# driver.net
KiCad netlist of a schematic drawn in EAGLE
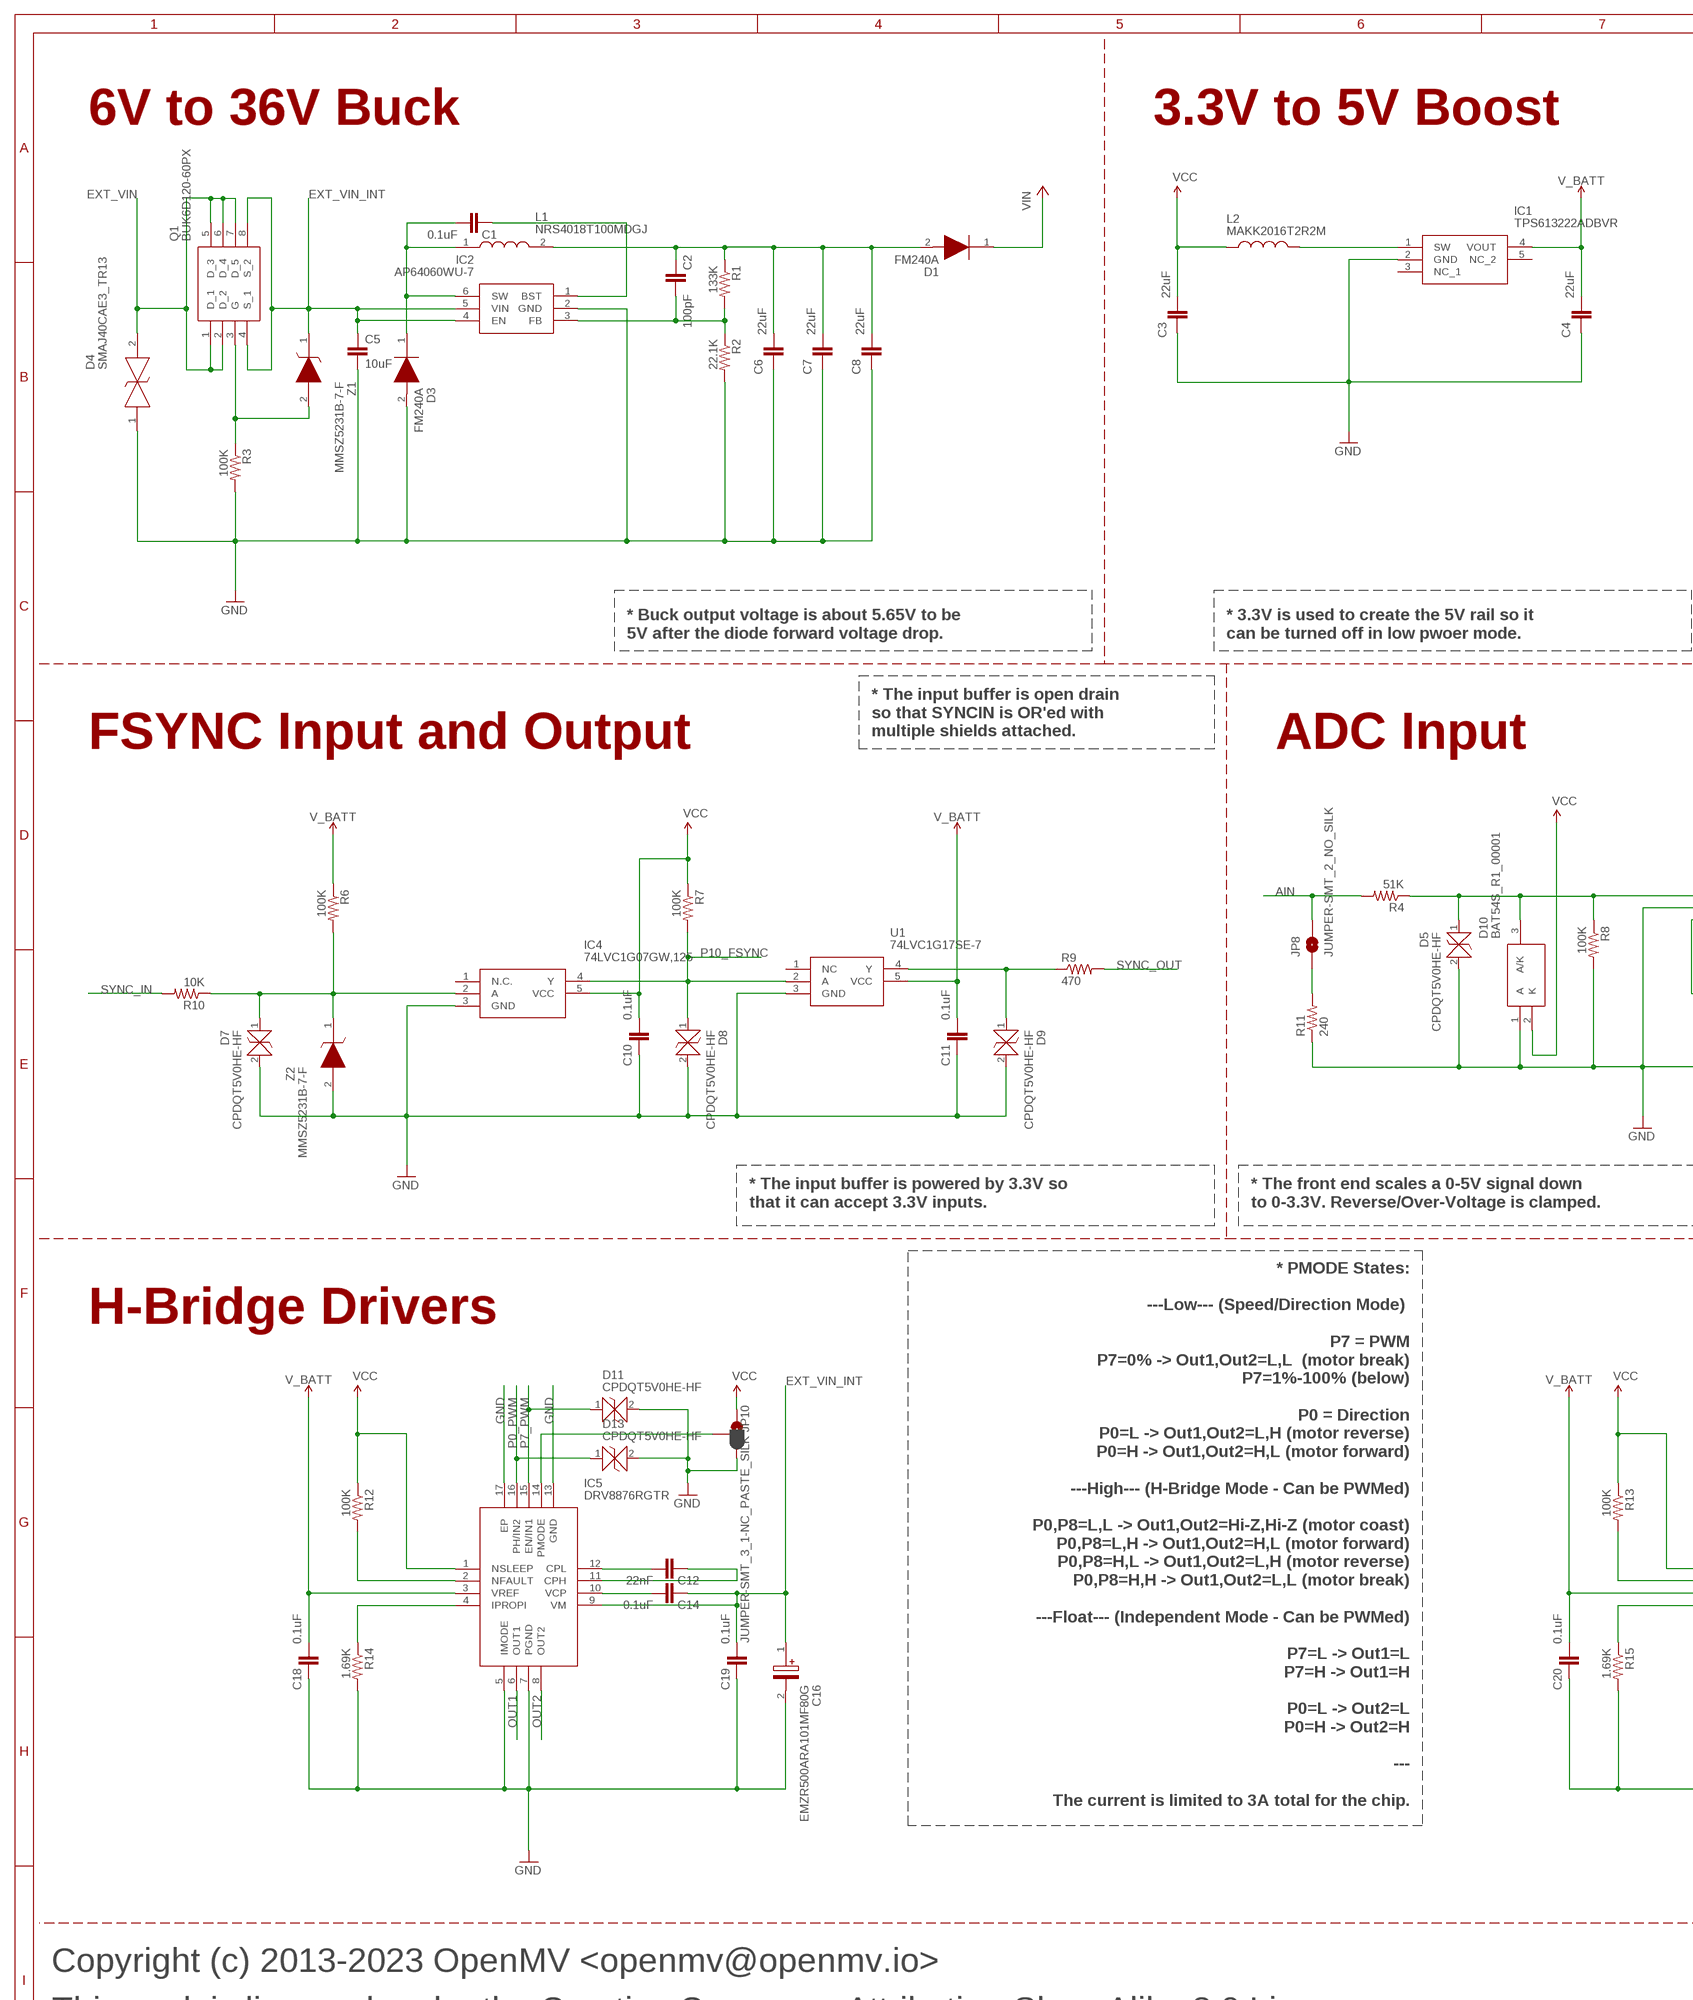
[diagram p0: schematic, sheet 1, part 1 of 2]
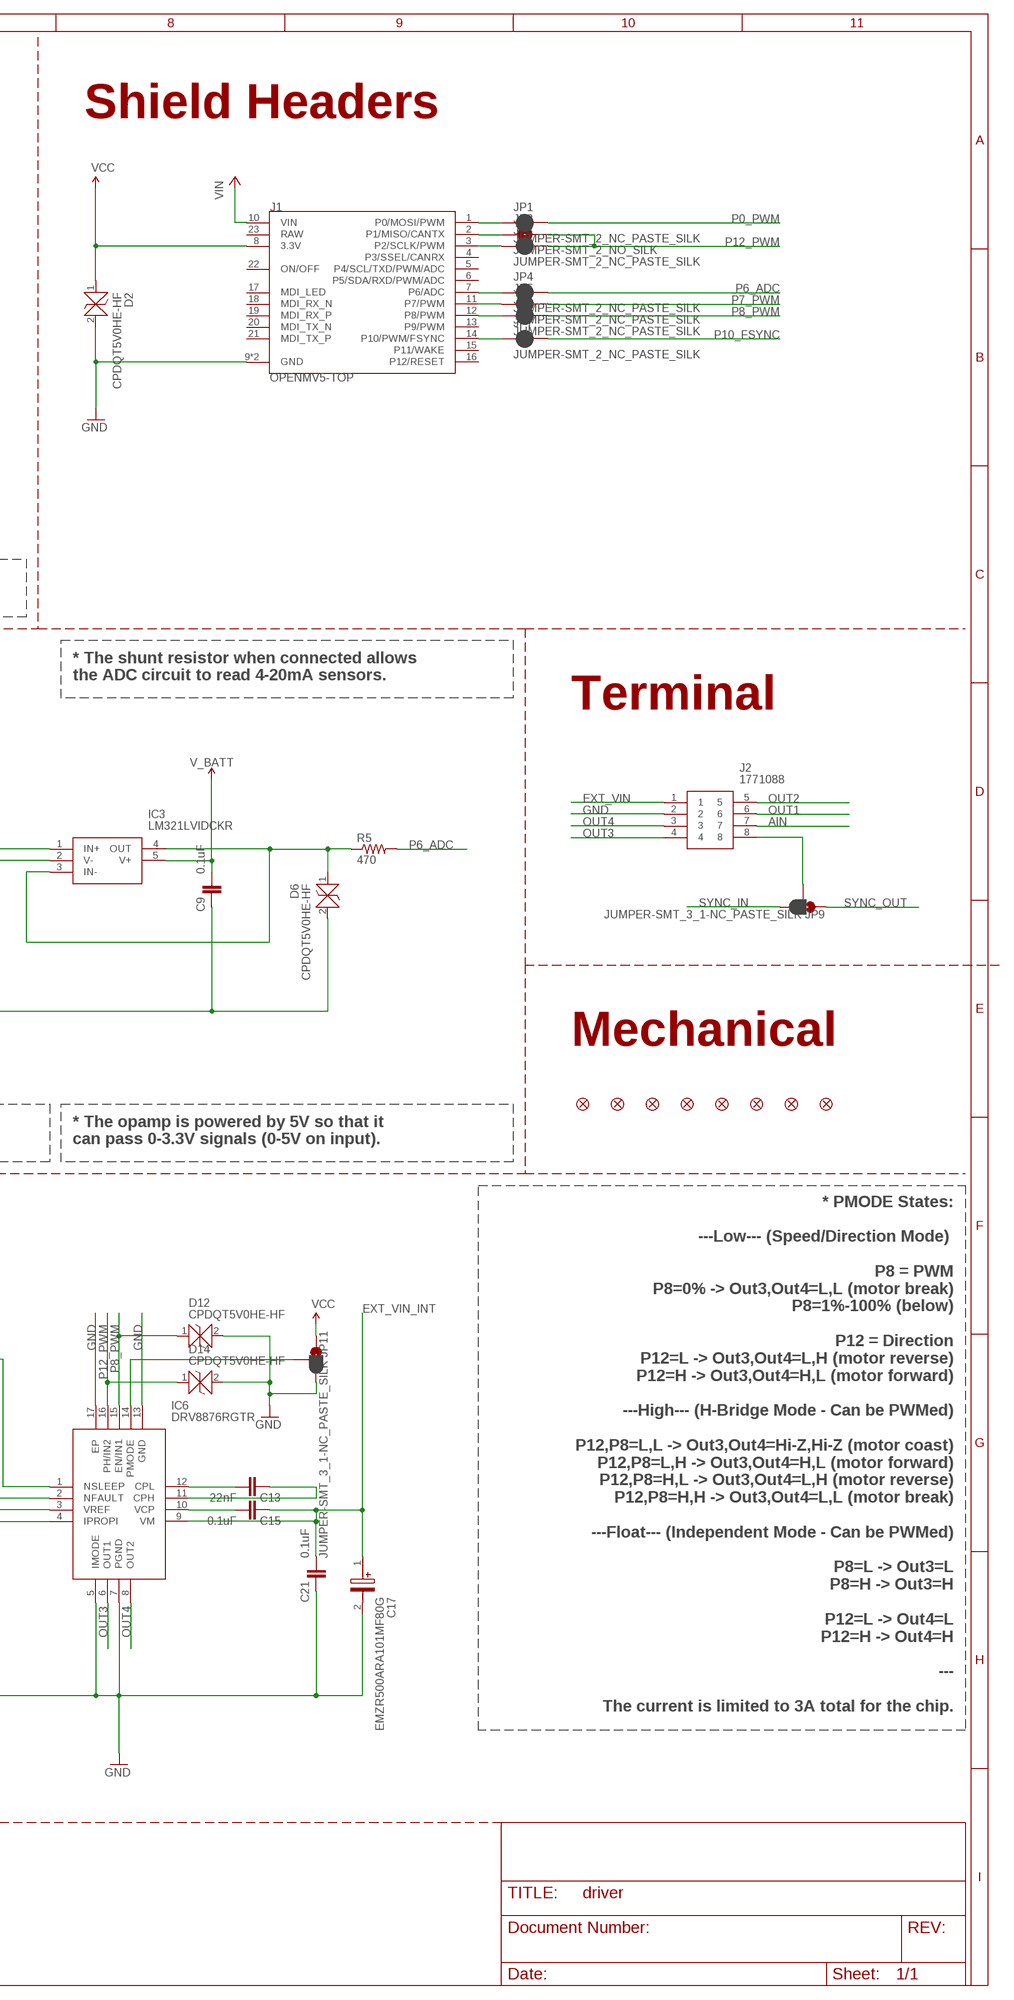
[diagram p1: schematic, sheet 1, part 2 of 2]

(export (version "E")
  (design (tool "Eeschema 10.0.6"))
  (components
    (comp (ref "C1")
      (value "0.1uF")
      (footprint "eagle-import:0402-CAP")
      (fields (field (name "MPN") "GRM155R71H104KE14D"))
      (libsource (lib "eagle-import") (part "CAP0402-CAP"))
    )
    (comp (ref "C2")
      (value "100pF")
      (footprint "eagle-import:0402-CAP")
      (fields (field (name "MPN") "CC0402JRNPO9BN101"))
      (libsource (lib "eagle-import") (part "CAP0402-CAP"))
    )
    (comp (ref "C3")
      (value "22uF")
      (footprint "eagle-import:0805")
      (fields (field (name "MPN") "CL21A226MQQNNNE"))
      (libsource (lib "eagle-import") (part "22UF-0805-6.3V-20%"))
    )
    (comp (ref "C4")
      (value "22uF")
      (footprint "eagle-import:0805")
      (fields (field (name "MPN") "CL21A226MQQNNNE"))
      (libsource (lib "eagle-import") (part "22UF-0805-6.3V-20%"))
    )
    (comp (ref "C5")
      (value "10uF")
      (footprint "eagle-import:C0805")
      (fields (field (name "MPN") "GRM21BR61H106KE43K"))
      (libsource (lib "eagle-import") (part "C-EUC0805"))
    )
    (comp (ref "C6")
      (value "22uF")
      (footprint "eagle-import:0805")
      (fields (field (name "MPN") "CL21A226MQQNNNE"))
      (libsource (lib "eagle-import") (part "22UF-0805-6.3V-20%"))
    )
    (comp (ref "C7")
      (value "22uF")
      (footprint "eagle-import:0805")
      (fields (field (name "MPN") "CL21A226MQQNNNE"))
      (libsource (lib "eagle-import") (part "22UF-0805-6.3V-20%"))
    )
    (comp (ref "C8")
      (value "22uF")
      (footprint "eagle-import:0805")
      (fields (field (name "MPN") "CL21A226MQQNNNE"))
      (libsource (lib "eagle-import") (part "22UF-0805-6.3V-20%"))
    )
    (comp (ref "C9")
      (value "0.1uF")
      (footprint "eagle-import:0402-CAP")
      (fields (field (name "MPN") "GRM155R71H104KE14D"))
      (libsource (lib "eagle-import") (part "CAP0402-CAP"))
    )
    (comp (ref "C10")
      (value "0.1uF")
      (footprint "eagle-import:0402-CAP")
      (fields (field (name "MPN") "GRM155R71H104KE14D"))
      (libsource (lib "eagle-import") (part "CAP0402-CAP"))
    )
    (comp (ref "C11")
      (value "0.1uF")
      (footprint "eagle-import:0402-CAP")
      (fields (field (name "MPN") "GRM155R71H104KE14D"))
      (libsource (lib "eagle-import") (part "CAP0402-CAP"))
    )
    (comp (ref "C12")
      (value "22nF")
      (footprint "eagle-import:0402-CAP")
      (fields (field (name "MPN") "GRM155R71H223KA12D"))
      (libsource (lib "eagle-import") (part "CAP0402-CAP"))
    )
    (comp (ref "C13")
      (value "22nF")
      (footprint "eagle-import:0402-CAP")
      (fields (field (name "MPN") "GRM155R71H223KA12D"))
      (libsource (lib "eagle-import") (part "CAP0402-CAP"))
    )
    (comp (ref "C14")
      (value "0.1uF")
      (footprint "eagle-import:0402-CAP")
      (fields (field (name "MPN") "GRM155R71H104KE14D"))
      (libsource (lib "eagle-import") (part "CAP0402-CAP"))
    )
    (comp (ref "C15")
      (value "0.1uF")
      (footprint "eagle-import:0402-CAP")
      (fields (field (name "MPN") "GRM155R71H104KE14D"))
      (libsource (lib "eagle-import") (part "CAP0402-CAP"))
    )
    (comp (ref "C16")
      (value "EMZR500ARA101MF80G")
      (footprint "eagle-import:CAPAE660X820N")
      (fields (field (name "MOUSER_PART_NUMBER") "661-EMZR500ARA101MF8"))
      (libsource (lib "eagle-import") (part "EMZR500ARA101MF80G"))
    )
    (comp (ref "C17")
      (value "EMZR500ARA101MF80G")
      (footprint "eagle-import:CAPAE660X820N")
      (fields (field (name "MOUSER_PART_NUMBER") "661-EMZR500ARA101MF8"))
      (libsource (lib "eagle-import") (part "EMZR500ARA101MF80G"))
    )
    (comp (ref "C18")
      (value "0.1uF")
      (footprint "eagle-import:0402-CAP")
      (fields (field (name "MPN") "GRM155R71H104KE14D"))
      (libsource (lib "eagle-import") (part "CAP0402-CAP"))
    )
    (comp (ref "C19")
      (value "0.1uF")
      (footprint "eagle-import:0402-CAP")
      (fields (field (name "MPN") "GRM155R71H104KE14D"))
      (libsource (lib "eagle-import") (part "CAP0402-CAP"))
    )
    (comp (ref "C20")
      (value "0.1uF")
      (footprint "eagle-import:0402-CAP")
      (fields (field (name "MPN") "GRM155R71H104KE14D"))
      (libsource (lib "eagle-import") (part "CAP0402-CAP"))
    )
    (comp (ref "C21")
      (value "0.1uF")
      (footprint "eagle-import:0402-CAP")
      (fields (field (name "MPN") "GRM155R71H104KE14D"))
      (libsource (lib "eagle-import") (part "CAP0402-CAP"))
    )
    (comp (ref "D1")
      (value "FM240A")
      (footprint "eagle-import:DIOM5025X231N")
      (fields (field (name "MOUSER_PART_NUMBER") "583-FM240A"))
      (libsource (lib "eagle-import") (part "FM240A"))
    )
    (comp (ref "D2")
      (value "CPDQT5V0HE-HF")
      (footprint "eagle-import:CPDQT5V0HEHF")
      (libsource (lib "eagle-import") (part "CPDQT5V0HE-HF"))
    )
    (comp (ref "D3")
      (value "FM240A")
      (footprint "eagle-import:DIOM5025X231N")
      (fields (field (name "MOUSER_PART_NUMBER") "583-FM240A"))
      (libsource (lib "eagle-import") (part "FM240A"))
    )
    (comp (ref "D4")
      (value "SMAJ40CAE3_TR13")
      (footprint "eagle-import:SMAJ40CAE3TR13")
      (fields
        (field (name "MANUFACTURER_PART_NUMBER") "SMAJ40CAe3/TR13")
        (field (name "MOUSER_PART_NUMBER") "494-SMAJ40CAE3/TR13")
      )
      (libsource (lib "eagle-import") (part "SMAJ40CAE3_TR13"))
    )
    (comp (ref "D5")
      (value "CPDQT5V0HE-HF")
      (footprint "eagle-import:CPDQT5V0HEHF")
      (libsource (lib "eagle-import") (part "CPDQT5V0HE-HF"))
    )
    (comp (ref "D6")
      (value "CPDQT5V0HE-HF")
      (footprint "eagle-import:CPDQT5V0HEHF")
      (libsource (lib "eagle-import") (part "CPDQT5V0HE-HF"))
    )
    (comp (ref "D7")
      (value "CPDQT5V0HE-HF")
      (footprint "eagle-import:CPDQT5V0HEHF")
      (libsource (lib "eagle-import") (part "CPDQT5V0HE-HF"))
    )
    (comp (ref "D8")
      (value "CPDQT5V0HE-HF")
      (footprint "eagle-import:CPDQT5V0HEHF")
      (libsource (lib "eagle-import") (part "CPDQT5V0HE-HF"))
    )
    (comp (ref "D9")
      (value "CPDQT5V0HE-HF")
      (footprint "eagle-import:CPDQT5V0HEHF")
      (libsource (lib "eagle-import") (part "CPDQT5V0HE-HF"))
    )
    (comp (ref "D10")
      (value "BAT54S_R1_00001")
      (footprint "eagle-import:SOT95P240X110-3N")
      (fields (field (name "MOUSER_PART_NUMBER") "241-BAT54S_R1_00001"))
      (libsource (lib "eagle-import") (part "BAT54S_R1_00001"))
    )
    (comp (ref "D11")
      (value "CPDQT5V0HE-HF")
      (footprint "eagle-import:CPDQT5V0HEHF")
      (libsource (lib "eagle-import") (part "CPDQT5V0HE-HF"))
    )
    (comp (ref "D12")
      (value "CPDQT5V0HE-HF")
      (footprint "eagle-import:CPDQT5V0HEHF")
      (libsource (lib "eagle-import") (part "CPDQT5V0HE-HF"))
    )
    (comp (ref "D13")
      (value "CPDQT5V0HE-HF")
      (footprint "eagle-import:CPDQT5V0HEHF")
      (libsource (lib "eagle-import") (part "CPDQT5V0HE-HF"))
    )
    (comp (ref "D14")
      (value "CPDQT5V0HE-HF")
      (footprint "eagle-import:CPDQT5V0HEHF")
      (libsource (lib "eagle-import") (part "CPDQT5V0HE-HF"))
    )
    (comp (ref "FD1")
      (value "FIDUCIAL1X2")
      (footprint "eagle-import:FIDUCIAL-1X2")
      (libsource (lib "eagle-import") (part "FIDUCIAL1X2"))
    )
    (comp (ref "FD2")
      (value "FIDUCIAL1X2")
      (footprint "eagle-import:FIDUCIAL-1X2")
      (libsource (lib "eagle-import") (part "FIDUCIAL1X2"))
    )
    (comp (ref "FD3")
      (value "FIDUCIAL1X2")
      (footprint "eagle-import:FIDUCIAL-1X2")
      (libsource (lib "eagle-import") (part "FIDUCIAL1X2"))
    )
    (comp (ref "FD4")
      (value "FIDUCIAL1X2")
      (footprint "eagle-import:FIDUCIAL-1X2")
      (libsource (lib "eagle-import") (part "FIDUCIAL1X2"))
    )
    (comp (ref "FD5")
      (value "FIDUCIAL1X2")
      (footprint "eagle-import:FIDUCIAL-1X2")
      (libsource (lib "eagle-import") (part "FIDUCIAL1X2"))
    )
    (comp (ref "FD6")
      (value "FIDUCIAL1X2")
      (footprint "eagle-import:FIDUCIAL-1X2")
      (libsource (lib "eagle-import") (part "FIDUCIAL1X2"))
    )
    (comp (ref "FD7")
      (value "FIDUCIAL1X2")
      (footprint "eagle-import:FIDUCIAL-1X2")
      (libsource (lib "eagle-import") (part "FIDUCIAL1X2"))
    )
    (comp (ref "FD8")
      (value "FIDUCIAL1X2")
      (footprint "eagle-import:FIDUCIAL-1X2")
      (libsource (lib "eagle-import") (part "FIDUCIAL1X2"))
    )
    (comp (ref "IC1")
      (value "TPS613222ADBVR")
      (footprint "eagle-import:SOT95P280X145-5N")
      (fields (field (name "MOUSER_PART_NUMBER") "595-TPS613222ADBVR"))
      (libsource (lib "eagle-import") (part "TPS613222ADBVR"))
    )
    (comp (ref "IC2")
      (value "AP64060WU-7")
      (footprint "eagle-import:SOT95P280X100-6N")
      (fields (field (name "MOUSER_PART_NUMBER") "621-AP64060WU-7"))
      (libsource (lib "eagle-import") (part "AP64060WU-7"))
    )
    (comp (ref "IC3")
      (value "LM321LVIDCKR")
      (footprint "eagle-import:SOT65P210X110-5N")
      (fields (field (name "MOUSER_PART_NUMBER") "595-LM321LVIDCKR"))
      (libsource (lib "eagle-import") (part "LM321LVIDCKR"))
    )
    (comp (ref "IC4")
      (value "74LVC1G07GW,125")
      (footprint "eagle-import:SOT65P212X110-5N")
      (fields (field (name "MOUSER_PART_NUMBER") "771-74LVC1G07GW-G"))
      (libsource (lib "eagle-import") (part "74LVC1G07GW,125"))
    )
    (comp (ref "IC5")
      (value "DRV8876RGTR")
      (footprint "eagle-import:QFN50P300X300X100-17N")
      (fields (field (name "MOUSER_PART_NUMBER") "595-DRV8876RGTR"))
      (libsource (lib "eagle-import") (part "DRV8876RGTR"))
    )
    (comp (ref "IC6")
      (value "DRV8876RGTR")
      (footprint "eagle-import:QFN50P300X300X100-17N")
      (fields (field (name "MOUSER_PART_NUMBER") "595-DRV8876RGTR"))
      (libsource (lib "eagle-import") (part "DRV8876RGTR"))
    )
    (comp (ref "J1")
      (value "OPENMV5-TOP")
      (footprint "eagle-import:OPENMV5-TOP")
      (libsource (lib "eagle-import") (part "OPENMV5-TOP"))
    )
    (comp (ref "J2")
      (value "1771088")
      (footprint "eagle-import:1771088")
      (fields (field (name "MOUSER_PART_NUMBER") "651-1771088"))
      (libsource (lib "eagle-import") (part "1771088"))
    )
    (comp (ref "JP1")
      (value "JUMPER-SMT_2_NC_PASTE_SILK")
      (footprint "eagle-import:SMT-JUMPER_2_NC_PASTE_SILK")
      (libsource (lib "eagle-import") (part "JUMPER-SMT_2_NC_PASTE_SILK"))
    )
    (comp (ref "JP2")
      (value "JUMPER-SMT_2_NO_SILK")
      (footprint "eagle-import:SMT-JUMPER_2_NO_SILK")
      (libsource (lib "eagle-import") (part "JUMPER-SMT_2_NO_SILK"))
    )
    (comp (ref "JP3")
      (value "JUMPER-SMT_2_NC_PASTE_SILK")
      (footprint "eagle-import:SMT-JUMPER_2_NC_PASTE_SILK")
      (libsource (lib "eagle-import") (part "JUMPER-SMT_2_NC_PASTE_SILK"))
    )
    (comp (ref "JP4")
      (value "JUMPER-SMT_2_NC_PASTE_SILK")
      (footprint "eagle-import:SMT-JUMPER_2_NC_PASTE_SILK")
      (libsource (lib "eagle-import") (part "JUMPER-SMT_2_NC_PASTE_SILK"))
    )
    (comp (ref "JP5")
      (value "JUMPER-SMT_2_NC_PASTE_SILK")
      (footprint "eagle-import:SMT-JUMPER_2_NC_PASTE_SILK")
      (libsource (lib "eagle-import") (part "JUMPER-SMT_2_NC_PASTE_SILK"))
    )
    (comp (ref "JP6")
      (value "JUMPER-SMT_2_NC_PASTE_SILK")
      (footprint "eagle-import:SMT-JUMPER_2_NC_PASTE_SILK")
      (libsource (lib "eagle-import") (part "JUMPER-SMT_2_NC_PASTE_SILK"))
    )
    (comp (ref "JP7")
      (value "JUMPER-SMT_2_NC_PASTE_SILK")
      (footprint "eagle-import:SMT-JUMPER_2_NC_PASTE_SILK")
      (libsource (lib "eagle-import") (part "JUMPER-SMT_2_NC_PASTE_SILK"))
    )
    (comp (ref "JP8")
      (value "JUMPER-SMT_2_NO_SILK")
      (footprint "eagle-import:SMT-JUMPER_2_NO_SILK")
      (libsource (lib "eagle-import") (part "JUMPER-SMT_2_NO_SILK"))
    )
    (comp (ref "JP9")
      (value "JUMPER-SMT_3_1-NC_PASTE_SILK")
      (footprint "eagle-import:SMT-JUMPER_3_1-NC_PASTE_SILK")
      (libsource (lib "eagle-import") (part "JUMPER-SMT_3_1-NC_PASTE_SILK"))
    )
    (comp (ref "JP10")
      (value "JUMPER-SMT_3_1-NC_PASTE_SILK")
      (footprint "eagle-import:SMT-JUMPER_3_1-NC_PASTE_SILK")
      (libsource (lib "eagle-import") (part "JUMPER-SMT_3_1-NC_PASTE_SILK"))
    )
    (comp (ref "JP11")
      (value "JUMPER-SMT_3_1-NC_PASTE_SILK")
      (footprint "eagle-import:SMT-JUMPER_3_1-NC_PASTE_SILK")
      (libsource (lib "eagle-import") (part "JUMPER-SMT_3_1-NC_PASTE_SILK"))
    )
    (comp (ref "L1")
      (value "NRS4018T100MDGJ")
      (footprint "eagle-import:NRS4018T100MDGJ")
      (fields (field (name "MOUSER_PART_NUMBER") "963-NRS4018T100MDGJ"))
      (libsource (lib "eagle-import") (part "NRS4018T100MDGJ"))
    )
    (comp (ref "L2")
      (value "MAKK2016T2R2M")
      (footprint "eagle-import:INDC2016X100N")
      (fields (field (name "MF") "Taiyo Yuden"))
      (libsource (lib "eagle-import") (part "MAKK2016T2R2M"))
    )
    (comp (ref "Q1")
      (value "BUK6D120-60PX")
      (footprint "eagle-import:BUK6D12060PX")
      (fields (field (name "MOUSER_PART_NUMBER") "771-BUK6D120-60PX"))
      (libsource (lib "eagle-import") (part "BUK6D120-60PX"))
    )
    (comp (ref "R1")
      (value "133K")
      (footprint "eagle-import:0402-RES")
      (fields (field (name "MPN") "RC0402FR-07133KL"))
      (libsource (lib "eagle-import") (part "RESISTOR0402-RES"))
    )
    (comp (ref "R2")
      (value "22.1K")
      (footprint "eagle-import:0402-RES")
      (fields (field (name "MPN") "CR0402-FX-2212GLF"))
      (libsource (lib "eagle-import") (part "RESISTOR0402-RES"))
    )
    (comp (ref "R3")
      (value "100K")
      (footprint "eagle-import:0402-RES")
      (fields (field (name "MPN") "AC0402FR-07100KL"))
      (libsource (lib "eagle-import") (part "RESISTOR0402-RES"))
    )
    (comp (ref "R4")
      (value "51K")
      (footprint "eagle-import:0402-RES")
      (fields (field (name "MPN") "RC0402JR-0751KL"))
      (libsource (lib "eagle-import") (part "RESISTOR0402-RES"))
    )
    (comp (ref "R5")
      (value "470")
      (footprint "eagle-import:R0603")
      (fields (field (name "MPN") "CR0603-FX-4700ELF"))
      (libsource (lib "eagle-import") (part "R-US_R0603"))
    )
    (comp (ref "R6")
      (value "100K")
      (footprint "eagle-import:0402-RES")
      (fields (field (name "MPN") "AC0402FR-07100KL"))
      (libsource (lib "eagle-import") (part "RESISTOR0402-RES"))
    )
    (comp (ref "R7")
      (value "100K")
      (footprint "eagle-import:0402-RES")
      (fields (field (name "MPN") "AC0402FR-07100KL"))
      (libsource (lib "eagle-import") (part "RESISTOR0402-RES"))
    )
    (comp (ref "R8")
      (value "100K")
      (footprint "eagle-import:0402-RES")
      (fields (field (name "MPN") "AC0402FR-07100KL"))
      (libsource (lib "eagle-import") (part "RESISTOR0402-RES"))
    )
    (comp (ref "R9")
      (value "470")
      (footprint "eagle-import:R0603")
      (fields (field (name "MPN") "CR0603-FX-4700ELF"))
      (libsource (lib "eagle-import") (part "R-US_R0603"))
    )
    (comp (ref "R10")
      (value "10K")
      (footprint "eagle-import:0402-RES")
      (fields (field (name "MPN") "AC0402FR-1310KL"))
      (libsource (lib "eagle-import") (part "RESISTOR0402-RES"))
    )
    (comp (ref "R11")
      (value "240")
      (footprint "eagle-import:R0603")
      (fields (field (name "MPN") "RK73B1JTTD241J"))
      (libsource (lib "eagle-import") (part "R-US_R0603"))
    )
    (comp (ref "R12")
      (value "100K")
      (footprint "eagle-import:0402-RES")
      (fields (field (name "MPN") "AC0402FR-07100KL"))
      (libsource (lib "eagle-import") (part "RESISTOR0402-RES"))
    )
    (comp (ref "R13")
      (value "100K")
      (footprint "eagle-import:0402-RES")
      (fields (field (name "MPN") "AC0402FR-07100KL"))
      (libsource (lib "eagle-import") (part "RESISTOR0402-RES"))
    )
    (comp (ref "R14")
      (value "1.69K")
      (footprint "eagle-import:0402-RES")
      (fields (field (name "MPN") "RC0402FR-07169RL"))
      (libsource (lib "eagle-import") (part "RESISTOR0402-RES"))
    )
    (comp (ref "R15")
      (value "1.69K")
      (footprint "eagle-import:0402-RES")
      (fields (field (name "MPN") "RC0402FR-07169RL"))
      (libsource (lib "eagle-import") (part "RESISTOR0402-RES"))
    )
    (comp (ref "U1")
      (value "74LVC1G17SE-7")
      (footprint "eagle-import:SOT65P210X110-5N")
      (fields (field (name "MOUSER_PART_NUMBER") "621-74LVC1G17SE-7"))
      (libsource (lib "eagle-import") (part "74LVC1G17SE-7"))
    )
    (comp (ref "Z1")
      (value "MMSZ5231B-7-F")
      (footprint "eagle-import:SOD3716X145N")
      (fields (field (name "MOUSER_PART_NUMBER") "621-MMSZ5231B-F"))
      (libsource (lib "eagle-import") (part "MMSZ5231B-7-F"))
    )
    (comp (ref "Z2")
      (value "MMSZ5231B-7-F")
      (footprint "eagle-import:SOD3716X145N")
      (fields (field (name "MOUSER_PART_NUMBER") "621-MMSZ5231B-F"))
      (libsource (lib "eagle-import") (part "MMSZ5231B-7-F"))
    )
  )
  (nets
    (net (code "1") (name "/AIN") (class "Default")
      (node (ref "J2") (pin "7") (pinfunction "7_7") (pintype "bidirectional"))
      (node (ref "JP8") (pin "2") (pinfunction "2_2") (pintype "passive"))
      (node (ref "R4") (pin "2") (pinfunction "2_2") (pintype "passive"))
    )
    (net (code "2") (name "/EXT_VIN") (class "Default")
      (node (ref "D4") (pin "2") (pinfunction "2_2") (pintype "bidirectional"))
      (node (ref "J2") (pin "1") (pinfunction "1_1") (pintype "bidirectional"))
      (node (ref "Q1") (pin "1") (pinfunction "D_1_1") (pintype "bidirectional"))
      (node (ref "Q1") (pin "2") (pinfunction "D_2_2") (pintype "bidirectional"))
      (node (ref "Q1") (pin "5") (pinfunction "D_3_5") (pintype "bidirectional"))
      (node (ref "Q1") (pin "6") (pinfunction "D_4_6") (pintype "bidirectional"))
      (node (ref "Q1") (pin "7") (pinfunction "D_5_7") (pintype "bidirectional"))
    )
    (net (code "3") (name "/EXT_VIN_INT") (class "Default")
      (node (ref "C14") (pin "1") (pinfunction "1_1") (pintype "passive"))
      (node (ref "C15") (pin "1") (pinfunction "1_1") (pintype "passive"))
      (node (ref "C16") (pin "1") (pinfunction "+_1") (pintype "bidirectional"))
      (node (ref "C17") (pin "1") (pinfunction "+_1") (pintype "bidirectional"))
      (node (ref "C19") (pin "2") (pinfunction "2_2") (pintype "passive"))
      (node (ref "C21") (pin "2") (pinfunction "2_2") (pintype "passive"))
      (node (ref "C5") (pin "1") (pinfunction "1_1") (pintype "passive"))
      (node (ref "IC2") (pin "4") (pinfunction "EN_4") (pintype "bidirectional"))
      (node (ref "IC2") (pin "5") (pinfunction "VIN_5") (pintype "bidirectional"))
      (node (ref "IC5") (pin "9") (pinfunction "VM_9") (pintype "bidirectional"))
      (node (ref "IC6") (pin "9") (pinfunction "VM_9") (pintype "bidirectional"))
      (node (ref "Q1") (pin "4") (pinfunction "S_1_4") (pintype "bidirectional"))
      (node (ref "Q1") (pin "8") (pinfunction "S_2_8") (pintype "bidirectional"))
      (node (ref "Z1") (pin "1") (pinfunction "K_1") (pintype "bidirectional"))
    )
    (net (code "4") (name "/OUT1") (class "Default")
      (node (ref "IC5") (pin "6") (pinfunction "OUT1_6") (pintype "bidirectional"))
      (node (ref "J2") (pin "6") (pinfunction "6_6") (pintype "bidirectional"))
    )
    (net (code "5") (name "/OUT2") (class "Default")
      (node (ref "IC5") (pin "8") (pinfunction "OUT2_8") (pintype "bidirectional"))
      (node (ref "J2") (pin "5") (pinfunction "5_5") (pintype "bidirectional"))
    )
    (net (code "6") (name "/OUT3") (class "Default")
      (node (ref "IC6") (pin "6") (pinfunction "OUT1_6") (pintype "bidirectional"))
      (node (ref "J2") (pin "4") (pinfunction "4_4") (pintype "bidirectional"))
    )
    (net (code "7") (name "/OUT4") (class "Default")
      (node (ref "IC6") (pin "8") (pinfunction "OUT2_8") (pintype "bidirectional"))
      (node (ref "J2") (pin "3") (pinfunction "3_3") (pintype "bidirectional"))
    )
    (net (code "8") (name "/P0_PWM") (class "Default")
      (node (ref "D13") (pin "1") (pinfunction "1_1") (pintype "bidirectional"))
      (node (ref "IC5") (pin "16") (pinfunction "PH/IN2_16") (pintype "bidirectional"))
      (node (ref "JP1") (pin "2") (pinfunction "2_2") (pintype "passive"))
    )
    (net (code "9") (name "/P6_ADC") (class "Default")
      (node (ref "JP4") (pin "2") (pinfunction "2_2") (pintype "passive"))
      (node (ref "R5") (pin "2") (pinfunction "2_2") (pintype "passive"))
    )
    (net (code "10") (name "/P7_PWM") (class "Default")
      (node (ref "D11") (pin "1") (pinfunction "1_1") (pintype "bidirectional"))
      (node (ref "IC5") (pin "15") (pinfunction "EN/IN1_15") (pintype "bidirectional"))
      (node (ref "JP5") (pin "2") (pinfunction "2_2") (pintype "passive"))
    )
    (net (code "11") (name "/P8_PWM") (class "Default")
      (node (ref "D12") (pin "1") (pinfunction "1_1") (pintype "bidirectional"))
      (node (ref "IC6") (pin "15") (pinfunction "EN/IN1_15") (pintype "bidirectional"))
      (node (ref "JP6") (pin "2") (pinfunction "2_2") (pintype "passive"))
    )
    (net (code "12") (name "/P10_FSYNC") (class "Default")
      (node (ref "D8") (pin "1") (pinfunction "1_1") (pintype "bidirectional"))
      (node (ref "IC4") (pin "4") (pinfunction "Y_4") (pintype "bidirectional"))
      (node (ref "JP7") (pin "2") (pinfunction "2_2") (pintype "passive"))
      (node (ref "R7") (pin "2") (pinfunction "2_2") (pintype "passive"))
      (node (ref "U1") (pin "2") (pinfunction "A_2") (pintype "bidirectional"))
    )
    (net (code "13") (name "/P12_PWM") (class "Default")
      (node (ref "D14") (pin "1") (pinfunction "1_1") (pintype "bidirectional"))
      (node (ref "IC6") (pin "16") (pinfunction "PH/IN2_16") (pintype "bidirectional"))
      (node (ref "JP2") (pin "2") (pinfunction "2_2") (pintype "passive"))
      (node (ref "JP3") (pin "2") (pinfunction "2_2") (pintype "passive"))
    )
    (net (code "14") (name "/RAW") (class "Default")
      (node (ref "J1") (pin "23") (pinfunction "RAW_23") (pintype "power_in"))
    )
    (net (code "15") (name "/SYNC_IN") (class "Default")
      (node (ref "JP9") (pin "3") (pinfunction "3_3") (pintype "passive"))
      (node (ref "R10") (pin "2") (pinfunction "2_2") (pintype "passive"))
    )
    (net (code "16") (name "/SYNC_OUT") (class "Default")
      (node (ref "JP9") (pin "1") (pinfunction "1_1") (pintype "passive"))
      (node (ref "R9") (pin "2") (pinfunction "2_2") (pintype "passive"))
    )
    (net (code "17") (name "GND") (class "Default")
      (node (ref "C10") (pin "1") (pinfunction "1_1") (pintype "passive"))
      (node (ref "C11") (pin "1") (pinfunction "1_1") (pintype "passive"))
      (node (ref "C16") (pin "2") (pinfunction "-_2") (pintype "bidirectional"))
      (node (ref "C17") (pin "2") (pinfunction "-_2") (pintype "bidirectional"))
      (node (ref "C18") (pin "1") (pinfunction "1_1") (pintype "passive"))
      (node (ref "C19") (pin "1") (pinfunction "1_1") (pintype "passive"))
      (node (ref "C20") (pin "1") (pinfunction "1_1") (pintype "passive"))
      (node (ref "C21") (pin "1") (pinfunction "1_1") (pintype "passive"))
      (node (ref "C3") (pin "1") (pinfunction "1_1") (pintype "passive"))
      (node (ref "C4") (pin "1") (pinfunction "1_1") (pintype "passive"))
      (node (ref "C5") (pin "2") (pinfunction "2_2") (pintype "passive"))
      (node (ref "C6") (pin "1") (pinfunction "1_1") (pintype "passive"))
      (node (ref "C7") (pin "1") (pinfunction "1_1") (pintype "passive"))
      (node (ref "C8") (pin "1") (pinfunction "1_1") (pintype "passive"))
      (node (ref "C9") (pin "1") (pinfunction "1_1") (pintype "passive"))
      (node (ref "D10") (pin "1") (pinfunction "A_1") (pintype "bidirectional"))
      (node (ref "D11") (pin "2") (pinfunction "2_2") (pintype "bidirectional"))
      (node (ref "D12") (pin "2") (pinfunction "2_2") (pintype "bidirectional"))
      (node (ref "D13") (pin "2") (pinfunction "2_2") (pintype "bidirectional"))
      (node (ref "D14") (pin "2") (pinfunction "2_2") (pintype "bidirectional"))
      (node (ref "D2") (pin "2") (pinfunction "2_2") (pintype "bidirectional"))
      (node (ref "D3") (pin "2") (pinfunction "A_2") (pintype "bidirectional"))
      (node (ref "D4") (pin "1") (pinfunction "1_1") (pintype "bidirectional"))
      (node (ref "D5") (pin "2") (pinfunction "2_2") (pintype "bidirectional"))
      (node (ref "D6") (pin "2") (pinfunction "2_2") (pintype "bidirectional"))
      (node (ref "D7") (pin "2") (pinfunction "2_2") (pintype "bidirectional"))
      (node (ref "D8") (pin "2") (pinfunction "2_2") (pintype "bidirectional"))
      (node (ref "D9") (pin "2") (pinfunction "2_2") (pintype "bidirectional"))
      (node (ref "IC1") (pin "2") (pinfunction "GND_2") (pintype "bidirectional"))
      (node (ref "IC2") (pin "2") (pinfunction "GND_2") (pintype "bidirectional"))
      (node (ref "IC3") (pin "2") (pinfunction "V-_2") (pintype "input"))
      (node (ref "IC4") (pin "3") (pinfunction "GND_3") (pintype "bidirectional"))
      (node (ref "IC5") (pin "13") (pinfunction "GND_13") (pintype "bidirectional"))
      (node (ref "IC5") (pin "17") (pinfunction "EP_17") (pintype "bidirectional"))
      (node (ref "IC5") (pin "5") (pinfunction "IMODE_5") (pintype "bidirectional"))
      (node (ref "IC5") (pin "7") (pinfunction "PGND_7") (pintype "bidirectional"))
      (node (ref "IC6") (pin "13") (pinfunction "GND_13") (pintype "bidirectional"))
      (node (ref "IC6") (pin "17") (pinfunction "EP_17") (pintype "bidirectional"))
      (node (ref "IC6") (pin "5") (pinfunction "IMODE_5") (pintype "bidirectional"))
      (node (ref "IC6") (pin "7") (pinfunction "PGND_7") (pintype "bidirectional"))
      (node (ref "J1") (pin "24") (pinfunction "GND_24") (pintype "power_in"))
      (node (ref "J1") (pin "9") (pinfunction "GND_9") (pintype "power_in"))
      (node (ref "J2") (pin "2") (pinfunction "2_2") (pintype "bidirectional"))
      (node (ref "JP10") (pin "3") (pinfunction "3_3") (pintype "passive"))
      (node (ref "JP11") (pin "3") (pinfunction "3_3") (pintype "passive"))
      (node (ref "R11") (pin "1") (pinfunction "1_1") (pintype "passive"))
      (node (ref "R14") (pin "2") (pinfunction "2_2") (pintype "passive"))
      (node (ref "R15") (pin "2") (pinfunction "2_2") (pintype "passive"))
      (node (ref "R2") (pin "2") (pinfunction "2_2") (pintype "passive"))
      (node (ref "R3") (pin "2") (pinfunction "2_2") (pintype "passive"))
      (node (ref "R8") (pin "2") (pinfunction "2_2") (pintype "passive"))
      (node (ref "U1") (pin "3") (pinfunction "GND_3") (pintype "bidirectional"))
      (node (ref "Z2") (pin "2") (pinfunction "A_2") (pintype "bidirectional"))
    )
    (net (code "18") (name "Net-(D1-A)") (class "Default")
      (node (ref "C2") (pin "1") (pinfunction "1_1") (pintype "passive"))
      (node (ref "C6") (pin "2") (pinfunction "2_2") (pintype "passive"))
      (node (ref "C7") (pin "2") (pinfunction "2_2") (pintype "passive"))
      (node (ref "C8") (pin "2") (pinfunction "2_2") (pintype "passive"))
      (node (ref "D1") (pin "2") (pinfunction "A_2") (pintype "bidirectional"))
      (node (ref "L1") (pin "2") (pinfunction "2_2") (pintype "bidirectional"))
      (node (ref "R1") (pin "1") (pinfunction "1_1") (pintype "passive"))
    )
    (net (code "19") (name "Net-(D3-K)") (class "Default")
      (node (ref "C1") (pin "2") (pinfunction "2_2") (pintype "passive"))
      (node (ref "D3") (pin "1") (pinfunction "K_1") (pintype "bidirectional"))
      (node (ref "IC2") (pin "6") (pinfunction "SW_6") (pintype "bidirectional"))
      (node (ref "L1") (pin "1") (pinfunction "1_1") (pintype "bidirectional"))
    )
    (net (code "20") (name "Net-(D10-A{slash}K)") (class "Default")
      (node (ref "D10") (pin "3") (pinfunction "A/K_3") (pintype "bidirectional"))
      (node (ref "D5") (pin "1") (pinfunction "1_1") (pintype "bidirectional"))
      (node (ref "IC3") (pin "1") (pinfunction "IN+_1") (pintype "input"))
      (node (ref "R4") (pin "1") (pinfunction "1_1") (pintype "passive"))
      (node (ref "R8") (pin "1") (pinfunction "1_1") (pintype "passive"))
    )
    (net (code "21") (name "Net-(IC1-SW)") (class "Default")
      (node (ref "IC1") (pin "1") (pinfunction "SW_1") (pintype "bidirectional"))
      (node (ref "L2") (pin "2") (pinfunction "2_2") (pintype "passive"))
    )
    (net (code "22") (name "Net-(IC2-BST)") (class "Default")
      (node (ref "C1") (pin "1") (pinfunction "1_1") (pintype "passive"))
      (node (ref "IC2") (pin "1") (pinfunction "BST_1") (pintype "bidirectional"))
    )
    (net (code "23") (name "Net-(IC2-FB)") (class "Default")
      (node (ref "C2") (pin "2") (pinfunction "2_2") (pintype "passive"))
      (node (ref "IC2") (pin "3") (pinfunction "FB_3") (pintype "bidirectional"))
      (node (ref "R1") (pin "2") (pinfunction "2_2") (pintype "passive"))
      (node (ref "R2") (pin "1") (pinfunction "1_1") (pintype "passive"))
    )
    (net (code "24") (name "Net-(IC3-IN-)") (class "Default")
      (node (ref "D6") (pin "1") (pinfunction "1_1") (pintype "bidirectional"))
      (node (ref "IC3") (pin "3") (pinfunction "IN-_3") (pintype "input"))
      (node (ref "IC3") (pin "4") (pinfunction "OUT_4") (pintype "output"))
      (node (ref "R5") (pin "1") (pinfunction "1_1") (pintype "passive"))
    )
    (net (code "25") (name "Net-(IC4-A)") (class "Default")
      (node (ref "D7") (pin "1") (pinfunction "1_1") (pintype "bidirectional"))
      (node (ref "IC4") (pin "2") (pinfunction "A_2") (pintype "bidirectional"))
      (node (ref "R10") (pin "1") (pinfunction "1_1") (pintype "passive"))
      (node (ref "R6") (pin "2") (pinfunction "2_2") (pintype "passive"))
      (node (ref "Z2") (pin "1") (pinfunction "K_1") (pintype "bidirectional"))
    )
    (net (code "26") (name "Net-(IC5-CPH)") (class "Default")
      (node (ref "C12") (pin "1") (pinfunction "1_1") (pintype "passive"))
      (node (ref "IC5") (pin "11") (pinfunction "CPH_11") (pintype "bidirectional"))
    )
    (net (code "27") (name "Net-(IC5-CPL)") (class "Default")
      (node (ref "C12") (pin "2") (pinfunction "2_2") (pintype "passive"))
      (node (ref "IC5") (pin "12") (pinfunction "CPL_12") (pintype "bidirectional"))
    )
    (net (code "28") (name "Net-(IC5-IPROPI)") (class "Default")
      (node (ref "IC5") (pin "4") (pinfunction "IPROPI_4") (pintype "bidirectional"))
      (node (ref "R14") (pin "1") (pinfunction "1_1") (pintype "passive"))
    )
    (net (code "29") (name "Net-(IC5-NFAULT)") (class "Default")
      (node (ref "IC5") (pin "2") (pinfunction "NFAULT_2") (pintype "bidirectional"))
      (node (ref "R12") (pin "2") (pinfunction "2_2") (pintype "passive"))
    )
    (net (code "30") (name "Net-(IC5-PMODE)") (class "Default")
      (node (ref "IC5") (pin "14") (pinfunction "PMODE_14") (pintype "bidirectional"))
      (node (ref "JP10") (pin "2") (pinfunction "2_2") (pintype "passive"))
    )
    (net (code "31") (name "Net-(IC5-VCP)") (class "Default")
      (node (ref "C14") (pin "2") (pinfunction "2_2") (pintype "passive"))
      (node (ref "IC5") (pin "10") (pinfunction "VCP_10") (pintype "bidirectional"))
    )
    (net (code "32") (name "Net-(IC6-CPH)") (class "Default")
      (node (ref "C13") (pin "1") (pinfunction "1_1") (pintype "passive"))
      (node (ref "IC6") (pin "11") (pinfunction "CPH_11") (pintype "bidirectional"))
    )
    (net (code "33") (name "Net-(IC6-CPL)") (class "Default")
      (node (ref "C13") (pin "2") (pinfunction "2_2") (pintype "passive"))
      (node (ref "IC6") (pin "12") (pinfunction "CPL_12") (pintype "bidirectional"))
    )
    (net (code "34") (name "Net-(IC6-IPROPI)") (class "Default")
      (node (ref "IC6") (pin "4") (pinfunction "IPROPI_4") (pintype "bidirectional"))
      (node (ref "R15") (pin "1") (pinfunction "1_1") (pintype "passive"))
    )
    (net (code "35") (name "Net-(IC6-NFAULT)") (class "Default")
      (node (ref "IC6") (pin "2") (pinfunction "NFAULT_2") (pintype "bidirectional"))
      (node (ref "R13") (pin "2") (pinfunction "2_2") (pintype "passive"))
    )
    (net (code "36") (name "Net-(IC6-PMODE)") (class "Default")
      (node (ref "IC6") (pin "14") (pinfunction "PMODE_14") (pintype "bidirectional"))
      (node (ref "JP11") (pin "2") (pinfunction "2_2") (pintype "passive"))
    )
    (net (code "37") (name "Net-(IC6-VCP)") (class "Default")
      (node (ref "C15") (pin "2") (pinfunction "2_2") (pintype "passive"))
      (node (ref "IC6") (pin "10") (pinfunction "VCP_10") (pintype "bidirectional"))
    )
    (net (code "38") (name "Net-(J1-P0{slash}MOSI{slash}PWM)") (class "Default")
      (node (ref "J1") (pin "1") (pinfunction "P0/MOSI/PWM_1") (pintype "bidirectional"))
      (node (ref "JP1") (pin "1") (pinfunction "1_1") (pintype "passive"))
    )
    (net (code "39") (name "Net-(J1-P1{slash}MISO{slash}CANTX)") (class "Default")
      (node (ref "J1") (pin "2") (pinfunction "P1/MISO/CANTX_2") (pintype "bidirectional"))
      (node (ref "JP2") (pin "1") (pinfunction "1_1") (pintype "passive"))
    )
    (net (code "40") (name "Net-(J1-P2{slash}SCLK{slash}PWM)") (class "Default")
      (node (ref "J1") (pin "3") (pinfunction "P2/SCLK/PWM_3") (pintype "bidirectional"))
      (node (ref "JP3") (pin "1") (pinfunction "1_1") (pintype "passive"))
    )
    (net (code "41") (name "Net-(J1-P6{slash}ADC)") (class "Default")
      (node (ref "J1") (pin "7") (pinfunction "P6/ADC_7") (pintype "bidirectional"))
      (node (ref "JP4") (pin "1") (pinfunction "1_1") (pintype "passive"))
    )
    (net (code "42") (name "Net-(J1-P7{slash}PWM)") (class "Default")
      (node (ref "J1") (pin "11") (pinfunction "P7/PWM_11") (pintype "bidirectional"))
      (node (ref "JP5") (pin "1") (pinfunction "1_1") (pintype "passive"))
    )
    (net (code "43") (name "Net-(J1-P8{slash}PWM)") (class "Default")
      (node (ref "J1") (pin "12") (pinfunction "P8/PWM_12") (pintype "bidirectional"))
      (node (ref "JP6") (pin "1") (pinfunction "1_1") (pintype "passive"))
    )
    (net (code "44") (name "Net-(J1-P10{slash}PWM{slash}FSYNC)") (class "Default")
      (node (ref "J1") (pin "14") (pinfunction "P10/PWM/FSYNC_14") (pintype "bidirectional"))
      (node (ref "JP7") (pin "1") (pinfunction "1_1") (pintype "passive"))
    )
    (net (code "45") (name "Net-(J2-Pad8)") (class "Default")
      (node (ref "J2") (pin "8") (pinfunction "8_8") (pintype "bidirectional"))
      (node (ref "JP9") (pin "2") (pinfunction "2_2") (pintype "passive"))
    )
    (net (code "46") (name "Net-(JP8-Pad1)") (class "Default")
      (node (ref "JP8") (pin "1") (pinfunction "1_1") (pintype "passive"))
      (node (ref "R11") (pin "2") (pinfunction "2_2") (pintype "passive"))
    )
    (net (code "47") (name "Net-(Q1-G)") (class "Default")
      (node (ref "Q1") (pin "3") (pinfunction "G_3") (pintype "bidirectional"))
      (node (ref "R3") (pin "1") (pinfunction "1_1") (pintype "passive"))
      (node (ref "Z1") (pin "2") (pinfunction "A_2") (pintype "bidirectional"))
    )
    (net (code "48") (name "Net-(U1-Y)") (class "Default")
      (node (ref "D9") (pin "1") (pinfunction "1_1") (pintype "bidirectional"))
      (node (ref "R9") (pin "1") (pinfunction "1_1") (pintype "passive"))
      (node (ref "U1") (pin "4") (pinfunction "Y_4") (pintype "bidirectional"))
    )
    (net (code "49") (name "VCC") (class "Default")
      (node (ref "C10") (pin "2") (pinfunction "2_2") (pintype "passive"))
      (node (ref "C3") (pin "2") (pinfunction "2_2") (pintype "passive"))
      (node (ref "D10") (pin "2") (pinfunction "K_2") (pintype "bidirectional"))
      (node (ref "D2") (pin "1") (pinfunction "1_1") (pintype "bidirectional"))
      (node (ref "IC4") (pin "5") (pinfunction "VCC_5") (pintype "bidirectional"))
      (node (ref "IC5") (pin "1") (pinfunction "NSLEEP_1") (pintype "bidirectional"))
      (node (ref "IC6") (pin "1") (pinfunction "NSLEEP_1") (pintype "bidirectional"))
      (node (ref "J1") (pin "8") (pinfunction "3.3V_8") (pintype "power_in"))
      (node (ref "JP10") (pin "1") (pinfunction "1_1") (pintype "passive"))
      (node (ref "JP11") (pin "1") (pinfunction "1_1") (pintype "passive"))
      (node (ref "L2") (pin "1") (pinfunction "1_1") (pintype "passive"))
      (node (ref "R12") (pin "1") (pinfunction "1_1") (pintype "passive"))
      (node (ref "R13") (pin "1") (pinfunction "1_1") (pintype "passive"))
      (node (ref "R7") (pin "1") (pinfunction "1_1") (pintype "passive"))
    )
    (net (code "50") (name "VIN") (class "Default")
      (node (ref "D1") (pin "1") (pinfunction "K_1") (pintype "bidirectional"))
      (node (ref "J1") (pin "10") (pinfunction "VIN_10") (pintype "power_in"))
    )
    (net (code "51") (name "V_BATT") (class "Default")
      (node (ref "C11") (pin "2") (pinfunction "2_2") (pintype "passive"))
      (node (ref "C18") (pin "2") (pinfunction "2_2") (pintype "passive"))
      (node (ref "C20") (pin "2") (pinfunction "2_2") (pintype "passive"))
      (node (ref "C4") (pin "2") (pinfunction "2_2") (pintype "passive"))
      (node (ref "C9") (pin "2") (pinfunction "2_2") (pintype "passive"))
      (node (ref "IC1") (pin "4") (pinfunction "VOUT_4") (pintype "bidirectional"))
      (node (ref "IC3") (pin "5") (pinfunction "V+_5") (pintype "input"))
      (node (ref "IC5") (pin "3") (pinfunction "VREF_3") (pintype "bidirectional"))
      (node (ref "IC6") (pin "3") (pinfunction "VREF_3") (pintype "bidirectional"))
      (node (ref "R6") (pin "1") (pinfunction "1_1") (pintype "passive"))
      (node (ref "U1") (pin "5") (pinfunction "VCC_5") (pintype "bidirectional"))
    )
    (net (code "52") (name "unconnected-(IC1-NC_1-Pad3)") (class "Default")
      (node (ref "IC1") (pin "3") (pinfunction "NC_1_3") (pintype "bidirectional"))
    )
    (net (code "53") (name "unconnected-(IC1-NC_2-Pad5)") (class "Default")
      (node (ref "IC1") (pin "5") (pinfunction "NC_2_5") (pintype "bidirectional"))
    )
    (net (code "54") (name "unconnected-(IC4-N.C.-Pad1)") (class "Default")
      (node (ref "IC4") (pin "1") (pinfunction "N.C._1") (pintype "no_connect"))
    )
    (net (code "55") (name "unconnected-(J1-MDI_LED-Pad17)") (class "Default")
      (node (ref "J1") (pin "17") (pinfunction "MDI_LED_17") (pintype "bidirectional"))
    )
    (net (code "56") (name "unconnected-(J1-MDI_RX_N-Pad18)") (class "Default")
      (node (ref "J1") (pin "18") (pinfunction "MDI_RX_N_18") (pintype "bidirectional"))
    )
    (net (code "57") (name "unconnected-(J1-MDI_RX_P-Pad19)") (class "Default")
      (node (ref "J1") (pin "19") (pinfunction "MDI_RX_P_19") (pintype "bidirectional"))
    )
    (net (code "58") (name "unconnected-(J1-MDI_TX_N-Pad20)") (class "Default")
      (node (ref "J1") (pin "20") (pinfunction "MDI_TX_N_20") (pintype "bidirectional"))
    )
    (net (code "59") (name "unconnected-(J1-MDI_TX_P-Pad21)") (class "Default")
      (node (ref "J1") (pin "21") (pinfunction "MDI_TX_P_21") (pintype "bidirectional"))
    )
    (net (code "60") (name "unconnected-(J1-ON{slash}OFF-Pad22)") (class "Default")
      (node (ref "J1") (pin "22") (pinfunction "ON/OFF_22") (pintype "bidirectional"))
    )
    (net (code "61") (name "unconnected-(J1-P3{slash}SSEL{slash}CANRX-Pad4)") (class "Default")
      (node (ref "J1") (pin "4") (pinfunction "P3/SSEL/CANRX_4") (pintype "bidirectional"))
    )
    (net (code "62") (name "unconnected-(J1-P4{slash}SCL{slash}TXD{slash}PWM{slash}ADC-Pad5)") (class "Default")
      (node (ref "J1") (pin "5") (pinfunction "P4/SCL/TXD/PWM/ADC_5") (pintype "bidirectional"))
    )
    (net (code "63") (name "unconnected-(J1-P5{slash}SDA{slash}RXD{slash}PWM{slash}ADC-Pad6)") (class "Default")
      (node (ref "J1") (pin "6") (pinfunction "P5/SDA/RXD/PWM/ADC_6") (pintype "bidirectional"))
    )
    (net (code "64") (name "unconnected-(J1-P9{slash}PWM-Pad13)") (class "Default")
      (node (ref "J1") (pin "13") (pinfunction "P9/PWM_13") (pintype "bidirectional"))
    )
    (net (code "65") (name "unconnected-(J1-P11{slash}WAKE-Pad15)") (class "Default")
      (node (ref "J1") (pin "15") (pinfunction "P11/WAKE_15") (pintype "bidirectional"))
    )
    (net (code "66") (name "unconnected-(J1-P12{slash}RESET-Pad16)") (class "Default")
      (node (ref "J1") (pin "16") (pinfunction "P12/RESET_16") (pintype "bidirectional"))
    )
    (net (code "67") (name "unconnected-(U1-NC-Pad1)") (class "Default")
      (node (ref "U1") (pin "1") (pinfunction "NC_1") (pintype "no_connect"))
    )
  )
)
